# DAC.net
KiCad netlist of a schematic drawn in Altium Designer
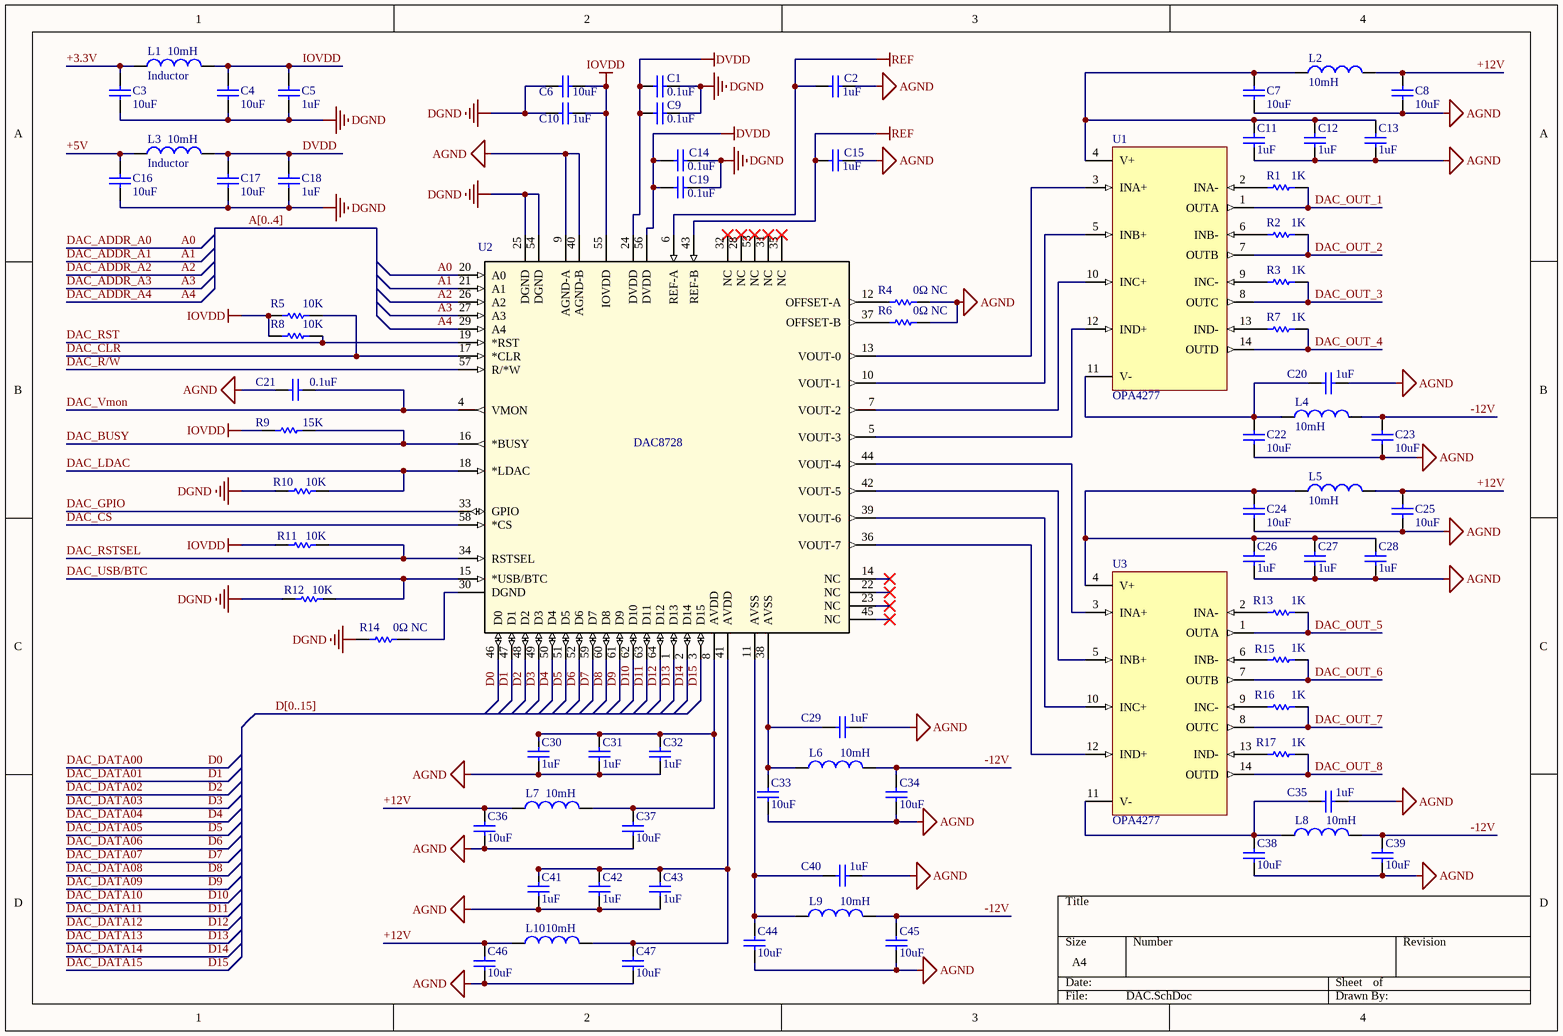
[diagram p0: DAC.SchDoc]

(export (version "E")
  (design (tool "Eeschema 10.0.6"))
  (components
    (comp (ref "C1")
      (value "0.1uF")
      (footprint "1608[0603]")
      (description "Capacitor")
      (fields (field (name "Comment") "Cap") (field (name "PUBLISHER") "Altium Limited"))
      (libsource (lib "Miscellaneous Devices") (part "Cap"))
    )
    (comp (ref "C2")
      (value "1uF")
      (footprint "1608[0603]")
      (description "Capacitor")
      (fields (field (name "Comment") "Cap") (field (name "PUBLISHER") "Altium Limited"))
      (libsource (lib "Miscellaneous Devices") (part "Cap"))
    )
    (comp (ref "C3")
      (value "10uF")
      (footprint "1608[0603]")
      (description "Capacitor")
      (fields (field (name "Comment") "Cap") (field (name "PUBLISHER") "Altium Limited"))
      (libsource (lib "Miscellaneous Devices") (part "Cap"))
    )
    (comp (ref "C4")
      (value "10uF")
      (footprint "1608[0603]")
      (description "Capacitor")
      (fields (field (name "Comment") "Cap") (field (name "PUBLISHER") "Altium Limited"))
      (libsource (lib "Miscellaneous Devices") (part "Cap"))
    )
    (comp (ref "C5")
      (value "1uF")
      (footprint "1608[0603]")
      (description "Capacitor")
      (fields (field (name "Comment") "Cap") (field (name "PUBLISHER") "Altium Limited"))
      (libsource (lib "Miscellaneous Devices") (part "Cap"))
    )
    (comp (ref "C6")
      (value "10uF")
      (footprint "1608[0603]")
      (description "Capacitor")
      (fields (field (name "Comment") "Cap") (field (name "PUBLISHER") "Altium Limited"))
      (libsource (lib "Miscellaneous Devices") (part "Cap"))
    )
    (comp (ref "C7")
      (value "10uF")
      (footprint "1608[0603]")
      (description "Capacitor")
      (fields (field (name "Comment") "Cap") (field (name "PUBLISHER") "Altium Limited"))
      (libsource (lib "Miscellaneous Devices") (part "Cap"))
    )
    (comp (ref "C8")
      (value "10uF")
      (footprint "1608[0603]")
      (description "Capacitor")
      (fields (field (name "Comment") "Cap") (field (name "PUBLISHER") "Altium Limited"))
      (libsource (lib "Miscellaneous Devices") (part "Cap"))
    )
    (comp (ref "C9")
      (value "0.1uF")
      (footprint "1608[0603]")
      (description "Capacitor")
      (fields (field (name "Comment") "Cap") (field (name "PUBLISHER") "Altium Limited"))
      (libsource (lib "Miscellaneous Devices") (part "Cap"))
    )
    (comp (ref "C10")
      (value "1uF")
      (footprint "1608[0603]")
      (description "Capacitor")
      (fields (field (name "Comment") "Cap") (field (name "PUBLISHER") "Altium Limited"))
      (libsource (lib "Miscellaneous Devices") (part "Cap"))
    )
    (comp (ref "C11")
      (value "1uF")
      (footprint "1608[0603]")
      (description "Capacitor")
      (fields (field (name "Comment") "Cap") (field (name "PUBLISHER") "Altium Limited"))
      (libsource (lib "Miscellaneous Devices") (part "Cap"))
    )
    (comp (ref "C12")
      (value "1uF")
      (footprint "1608[0603]")
      (description "Capacitor")
      (fields (field (name "Comment") "Cap") (field (name "PUBLISHER") "Altium Limited"))
      (libsource (lib "Miscellaneous Devices") (part "Cap"))
    )
    (comp (ref "C13")
      (value "1uF")
      (footprint "1608[0603]")
      (description "Capacitor")
      (fields (field (name "Comment") "Cap") (field (name "PUBLISHER") "Altium Limited"))
      (libsource (lib "Miscellaneous Devices") (part "Cap"))
    )
    (comp (ref "C14")
      (value "0.1uF")
      (footprint "1608[0603]")
      (description "Capacitor")
      (fields (field (name "Comment") "Cap") (field (name "PUBLISHER") "Altium Limited"))
      (libsource (lib "Miscellaneous Devices") (part "Cap"))
    )
    (comp (ref "C15")
      (value "1uF")
      (footprint "1608[0603]")
      (description "Capacitor")
      (fields (field (name "Comment") "Cap") (field (name "PUBLISHER") "Altium Limited"))
      (libsource (lib "Miscellaneous Devices") (part "Cap"))
    )
    (comp (ref "C16")
      (value "10uF")
      (footprint "1608[0603]")
      (description "Capacitor")
      (fields (field (name "Comment") "Cap") (field (name "PUBLISHER") "Altium Limited"))
      (libsource (lib "Miscellaneous Devices") (part "Cap"))
    )
    (comp (ref "C17")
      (value "10uF")
      (footprint "1608[0603]")
      (description "Capacitor")
      (fields (field (name "Comment") "Cap") (field (name "PUBLISHER") "Altium Limited"))
      (libsource (lib "Miscellaneous Devices") (part "Cap"))
    )
    (comp (ref "C18")
      (value "1uF")
      (footprint "1608[0603]")
      (description "Capacitor")
      (fields (field (name "Comment") "Cap") (field (name "PUBLISHER") "Altium Limited"))
      (libsource (lib "Miscellaneous Devices") (part "Cap"))
    )
    (comp (ref "C19")
      (value "0.1uF")
      (footprint "1608[0603]")
      (description "Capacitor")
      (fields (field (name "Comment") "Cap") (field (name "PUBLISHER") "Altium Limited"))
      (libsource (lib "Miscellaneous Devices") (part "Cap"))
    )
    (comp (ref "C20")
      (value "1uF")
      (footprint "1608[0603]")
      (description "Capacitor")
      (fields (field (name "Comment") "Cap") (field (name "PUBLISHER") "Altium Limited"))
      (libsource (lib "Miscellaneous Devices") (part "Cap"))
    )
    (comp (ref "C21")
      (value "0.1uF")
      (footprint "1608[0603]")
      (description "Capacitor")
      (fields (field (name "Comment") "Cap") (field (name "PUBLISHER") "Altium Limited"))
      (libsource (lib "Miscellaneous Devices") (part "Cap"))
    )
    (comp (ref "C22")
      (value "10uF")
      (footprint "1608[0603]")
      (description "Capacitor")
      (fields (field (name "Comment") "Cap") (field (name "PUBLISHER") "Altium Limited"))
      (libsource (lib "Miscellaneous Devices") (part "Cap"))
    )
    (comp (ref "C23")
      (value "10uF")
      (footprint "1608[0603]")
      (description "Capacitor")
      (fields (field (name "Comment") "Cap") (field (name "PUBLISHER") "Altium Limited"))
      (libsource (lib "Miscellaneous Devices") (part "Cap"))
    )
    (comp (ref "C24")
      (value "10uF")
      (footprint "1608[0603]")
      (description "Capacitor")
      (fields (field (name "Comment") "Cap") (field (name "PUBLISHER") "Altium Limited"))
      (libsource (lib "Miscellaneous Devices") (part "Cap"))
    )
    (comp (ref "C25")
      (value "10uF")
      (footprint "1608[0603]")
      (description "Capacitor")
      (fields (field (name "Comment") "Cap") (field (name "PUBLISHER") "Altium Limited"))
      (libsource (lib "Miscellaneous Devices") (part "Cap"))
    )
    (comp (ref "C26")
      (value "1uF")
      (footprint "1608[0603]")
      (description "Capacitor")
      (fields (field (name "Comment") "Cap") (field (name "PUBLISHER") "Altium Limited"))
      (libsource (lib "Miscellaneous Devices") (part "Cap"))
    )
    (comp (ref "C27")
      (value "1uF")
      (footprint "1608[0603]")
      (description "Capacitor")
      (fields (field (name "Comment") "Cap") (field (name "PUBLISHER") "Altium Limited"))
      (libsource (lib "Miscellaneous Devices") (part "Cap"))
    )
    (comp (ref "C28")
      (value "1uF")
      (footprint "1608[0603]")
      (description "Capacitor")
      (fields (field (name "Comment") "Cap") (field (name "PUBLISHER") "Altium Limited"))
      (libsource (lib "Miscellaneous Devices") (part "Cap"))
    )
    (comp (ref "C29")
      (value "1uF")
      (footprint "1608[0603]")
      (description "Capacitor")
      (fields (field (name "Comment") "Cap") (field (name "PUBLISHER") "Altium Limited"))
      (libsource (lib "Miscellaneous Devices") (part "Cap"))
    )
    (comp (ref "C30")
      (value "1uF")
      (footprint "1608[0603]")
      (description "Capacitor")
      (fields (field (name "Comment") "Cap") (field (name "PUBLISHER") "Altium Limited"))
      (libsource (lib "Miscellaneous Devices") (part "Cap"))
    )
    (comp (ref "C31")
      (value "1uF")
      (footprint "1608[0603]")
      (description "Capacitor")
      (fields (field (name "Comment") "Cap") (field (name "PUBLISHER") "Altium Limited"))
      (libsource (lib "Miscellaneous Devices") (part "Cap"))
    )
    (comp (ref "C32")
      (value "1uF")
      (footprint "1608[0603]")
      (description "Capacitor")
      (fields (field (name "Comment") "Cap") (field (name "PUBLISHER") "Altium Limited"))
      (libsource (lib "Miscellaneous Devices") (part "Cap"))
    )
    (comp (ref "C33")
      (value "10uF")
      (footprint "1608[0603]")
      (description "Capacitor")
      (fields (field (name "Comment") "Cap") (field (name "PUBLISHER") "Altium Limited"))
      (libsource (lib "Miscellaneous Devices") (part "Cap"))
    )
    (comp (ref "C34")
      (value "10uF")
      (footprint "1608[0603]")
      (description "Capacitor")
      (fields (field (name "Comment") "Cap") (field (name "PUBLISHER") "Altium Limited"))
      (libsource (lib "Miscellaneous Devices") (part "Cap"))
    )
    (comp (ref "C35")
      (value "1uF")
      (footprint "1608[0603]")
      (description "Capacitor")
      (fields (field (name "Comment") "Cap") (field (name "PUBLISHER") "Altium Limited"))
      (libsource (lib "Miscellaneous Devices") (part "Cap"))
    )
    (comp (ref "C36")
      (value "10uF")
      (footprint "1608[0603]")
      (description "Capacitor")
      (fields (field (name "Comment") "Cap") (field (name "PUBLISHER") "Altium Limited"))
      (libsource (lib "Miscellaneous Devices") (part "Cap"))
    )
    (comp (ref "C37")
      (value "10uF")
      (footprint "1608[0603]")
      (description "Capacitor")
      (fields (field (name "Comment") "Cap") (field (name "PUBLISHER") "Altium Limited"))
      (libsource (lib "Miscellaneous Devices") (part "Cap"))
    )
    (comp (ref "C38")
      (value "10uF")
      (footprint "1608[0603]")
      (description "Capacitor")
      (fields (field (name "Comment") "Cap") (field (name "PUBLISHER") "Altium Limited"))
      (libsource (lib "Miscellaneous Devices") (part "Cap"))
    )
    (comp (ref "C39")
      (value "10uF")
      (footprint "1608[0603]")
      (description "Capacitor")
      (fields (field (name "Comment") "Cap") (field (name "PUBLISHER") "Altium Limited"))
      (libsource (lib "Miscellaneous Devices") (part "Cap"))
    )
    (comp (ref "C40")
      (value "1uF")
      (footprint "1608[0603]")
      (description "Capacitor")
      (fields (field (name "Comment") "Cap") (field (name "PUBLISHER") "Altium Limited"))
      (libsource (lib "Miscellaneous Devices") (part "Cap"))
    )
    (comp (ref "C41")
      (value "1uF")
      (footprint "1608[0603]")
      (description "Capacitor")
      (fields (field (name "Comment") "Cap") (field (name "PUBLISHER") "Altium Limited"))
      (libsource (lib "Miscellaneous Devices") (part "Cap"))
    )
    (comp (ref "C42")
      (value "1uF")
      (footprint "1608[0603]")
      (description "Capacitor")
      (fields (field (name "Comment") "Cap") (field (name "PUBLISHER") "Altium Limited"))
      (libsource (lib "Miscellaneous Devices") (part "Cap"))
    )
    (comp (ref "C43")
      (value "1uF")
      (footprint "1608[0603]")
      (description "Capacitor")
      (fields (field (name "Comment") "Cap") (field (name "PUBLISHER") "Altium Limited"))
      (libsource (lib "Miscellaneous Devices") (part "Cap"))
    )
    (comp (ref "C44")
      (value "10uF")
      (footprint "1608[0603]")
      (description "Capacitor")
      (fields (field (name "Comment") "Cap") (field (name "PUBLISHER") "Altium Limited"))
      (libsource (lib "Miscellaneous Devices") (part "Cap"))
    )
    (comp (ref "C45")
      (value "10uF")
      (footprint "1608[0603]")
      (description "Capacitor")
      (fields (field (name "Comment") "Cap") (field (name "PUBLISHER") "Altium Limited"))
      (libsource (lib "Miscellaneous Devices") (part "Cap"))
    )
    (comp (ref "C46")
      (value "10uF")
      (footprint "1608[0603]")
      (description "Capacitor")
      (fields (field (name "Comment") "Cap") (field (name "PUBLISHER") "Altium Limited"))
      (libsource (lib "Miscellaneous Devices") (part "Cap"))
    )
    (comp (ref "C47")
      (value "10uF")
      (footprint "1608[0603]")
      (description "Capacitor")
      (fields (field (name "Comment") "Cap") (field (name "PUBLISHER") "Altium Limited"))
      (libsource (lib "Miscellaneous Devices") (part "Cap"))
    )
    (comp (ref "L1")
      (value "Inductor")
      (footprint "2029")
      (fields (field (name "ALTIUM_VALUE") "10mH") (field (name "PUBLISHER") "Altium Limited"))
      (libsource (lib "Miscellaneous Devices") (part "Inductor"))
    )
    (comp (ref "L2")
      (value "10mH")
      (footprint "2029")
      (description "Inductor")
      (fields (field (name "PUBLISHER") "Altium Limited"))
      (libsource (lib "") (part "Inductor_1"))
    )
    (comp (ref "L3")
      (value "Inductor")
      (footprint "2029")
      (fields (field (name "ALTIUM_VALUE") "10mH") (field (name "PUBLISHER") "Altium Limited"))
      (libsource (lib "Miscellaneous Devices") (part "Inductor"))
    )
    (comp (ref "L4")
      (value "10mH")
      (footprint "2029")
      (description "Inductor")
      (fields (field (name "PUBLISHER") "Altium Limited"))
      (libsource (lib "Miscellaneous Devices") (part "Inductor"))
    )
    (comp (ref "L5")
      (value "10mH")
      (footprint "2029")
      (description "Inductor")
      (fields (field (name "PUBLISHER") "Altium Limited"))
      (libsource (lib "") (part "Inductor_1"))
    )
    (comp (ref "L6")
      (value "10mH")
      (footprint "2029")
      (description "Inductor")
      (fields (field (name "PUBLISHER") "Altium Limited"))
      (libsource (lib "Miscellaneous Devices") (part "Inductor"))
    )
    (comp (ref "L7")
      (value "10mH")
      (footprint "2029")
      (description "Inductor")
      (fields (field (name "PUBLISHER") "Altium Limited"))
      (libsource (lib "Miscellaneous Devices") (part "Inductor"))
    )
    (comp (ref "L8")
      (value "10mH")
      (footprint "2029")
      (description "Inductor")
      (fields (field (name "PUBLISHER") "Altium Limited"))
      (libsource (lib "Miscellaneous Devices") (part "Inductor"))
    )
    (comp (ref "L9")
      (value "10mH")
      (footprint "2029")
      (description "Inductor")
      (fields (field (name "PUBLISHER") "Altium Limited"))
      (libsource (lib "Miscellaneous Devices") (part "Inductor"))
    )
    (comp (ref "L10")
      (value "10mH")
      (footprint "2029")
      (description "Inductor")
      (fields (field (name "PUBLISHER") "Altium Limited"))
      (libsource (lib "Miscellaneous Devices") (part "Inductor"))
    )
    (comp (ref "R1")
      (value "1K")
      (footprint "1608[0603]")
      (description "Resistor")
      (fields (field (name "Comment") "Res1") (field (name "PUBLISHER") "Altium Limited"))
      (libsource (lib "Miscellaneous Devices") (part "Res1"))
    )
    (comp (ref "R2")
      (value "1K")
      (footprint "1608[0603]")
      (description "Resistor")
      (fields (field (name "Comment") "Res1") (field (name "PUBLISHER") "Altium Limited"))
      (libsource (lib "Miscellaneous Devices") (part "Res1"))
    )
    (comp (ref "R3")
      (value "1K")
      (footprint "1608[0603]")
      (description "Resistor")
      (fields (field (name "Comment") "Res1") (field (name "PUBLISHER") "Altium Limited"))
      (libsource (lib "Miscellaneous Devices") (part "Res1"))
    )
    (comp (ref "R4")
      (value "0Ω NC")
      (footprint "1608[0603]")
      (description "Resistor")
      (fields (field (name "Comment") "Res1") (field (name "PUBLISHER") "Altium Limited"))
      (libsource (lib "Miscellaneous Devices") (part "Res1"))
    )
    (comp (ref "R5")
      (value "10K")
      (footprint "1608[0603]")
      (description "Resistor")
      (fields (field (name "Comment") "Res1") (field (name "PUBLISHER") "Altium Limited"))
      (libsource (lib "Miscellaneous Devices") (part "Res1"))
    )
    (comp (ref "R6")
      (value "0Ω NC")
      (footprint "1608[0603]")
      (description "Resistor")
      (fields (field (name "Comment") "Res1") (field (name "PUBLISHER") "Altium Limited"))
      (libsource (lib "Miscellaneous Devices") (part "Res1"))
    )
    (comp (ref "R7")
      (value "1K")
      (footprint "1608[0603]")
      (description "Resistor")
      (fields (field (name "Comment") "Res1") (field (name "PUBLISHER") "Altium Limited"))
      (libsource (lib "Miscellaneous Devices") (part "Res1"))
    )
    (comp (ref "R8")
      (value "10K")
      (footprint "1608[0603]")
      (description "Resistor")
      (fields (field (name "Comment") "Res1") (field (name "PUBLISHER") "Altium Limited"))
      (libsource (lib "Miscellaneous Devices") (part "Res1"))
    )
    (comp (ref "R9")
      (value "15K")
      (footprint "1608[0603]")
      (description "Resistor")
      (fields (field (name "Comment") "Res1") (field (name "PUBLISHER") "Altium Limited"))
      (libsource (lib "Miscellaneous Devices") (part "Res1"))
    )
    (comp (ref "R10")
      (value "10K")
      (footprint "1608[0603]")
      (description "Resistor")
      (fields (field (name "Comment") "Res1") (field (name "PUBLISHER") "Altium Limited"))
      (libsource (lib "Miscellaneous Devices") (part "Res1"))
    )
    (comp (ref "R11")
      (value "10K")
      (footprint "1608[0603]")
      (description "Resistor")
      (fields (field (name "Comment") "Res1") (field (name "PUBLISHER") "Altium Limited"))
      (libsource (lib "Miscellaneous Devices") (part "Res1"))
    )
    (comp (ref "R12")
      (value "10K")
      (footprint "1608[0603]")
      (description "Resistor")
      (fields (field (name "Comment") "Res1") (field (name "PUBLISHER") "Altium Limited"))
      (libsource (lib "Miscellaneous Devices") (part "Res1"))
    )
    (comp (ref "R13")
      (value "1K")
      (footprint "1608[0603]")
      (description "Resistor")
      (fields (field (name "Comment") "Res1") (field (name "PUBLISHER") "Altium Limited"))
      (libsource (lib "Miscellaneous Devices") (part "Res1"))
    )
    (comp (ref "R14")
      (value "0Ω NC")
      (footprint "1608[0603]")
      (description "Resistor")
      (fields (field (name "Comment") "Res1") (field (name "PUBLISHER") "Altium Limited"))
      (libsource (lib "Miscellaneous Devices") (part "Res1"))
    )
    (comp (ref "R15")
      (value "1K")
      (footprint "1608[0603]")
      (description "Resistor")
      (fields (field (name "Comment") "Res1") (field (name "PUBLISHER") "Altium Limited"))
      (libsource (lib "Miscellaneous Devices") (part "Res1"))
    )
    (comp (ref "R16")
      (value "1K")
      (footprint "1608[0603]")
      (description "Resistor")
      (fields (field (name "Comment") "Res1") (field (name "PUBLISHER") "Altium Limited"))
      (libsource (lib "Miscellaneous Devices") (part "Res1"))
    )
    (comp (ref "R17")
      (value "1K")
      (footprint "1608[0603]")
      (description "Resistor")
      (fields (field (name "Comment") "Res1") (field (name "PUBLISHER") "Altium Limited"))
      (libsource (lib "Miscellaneous Devices") (part "Res1"))
    )
    (comp (ref "U1")
      (value "OPA4277")
      (footprint "OPA4277_SOIC")
      (libsource (lib "DSP_FPGA_Lib") (part "OPA4277"))
    )
    (comp (ref "U2")
      (value "DAC8728")
      (footprint "DAC8728")
      (libsource (lib "DSP_FPGA_Lib") (part "DAC8728"))
    )
    (comp (ref "U3")
      (value "OPA4277")
      (footprint "OPA4277_SOIC")
      (libsource (lib "DSP_FPGA_Lib") (part "OPA4277"))
    )
  )
  (nets
    (net (code "1") (name "/+3.3V") (class "Default")
      (node (ref "C3") (pin "2") (pinfunction "2_2") (pintype "passive"))
      (node (ref "L1") (pin "1") (pinfunction "1_1") (pintype "passive"))
    )
    (net (code "2") (name "/+5V") (class "Default")
      (node (ref "C16") (pin "2") (pinfunction "2_2") (pintype "passive"))
      (node (ref "L3") (pin "1") (pinfunction "1_1") (pintype "passive"))
    )
    (net (code "3") (name "/+12V") (class "Default")
      (node (ref "C25") (pin "1") (pinfunction "1_1") (pintype "passive"))
      (node (ref "C36") (pin "1") (pinfunction "1_1") (pintype "passive"))
      (node (ref "C46") (pin "1") (pinfunction "1_1") (pintype "passive"))
      (node (ref "C8") (pin "1") (pinfunction "1_1") (pintype "passive"))
      (node (ref "L10") (pin "1") (pinfunction "1_1") (pintype "passive"))
      (node (ref "L2") (pin "1") (pinfunction "1_1") (pintype "passive"))
      (node (ref "L5") (pin "1") (pinfunction "1_1") (pintype "passive"))
      (node (ref "L7") (pin "1") (pinfunction "1_1") (pintype "passive"))
    )
    (net (code "4") (name "/-12V") (class "Default")
      (node (ref "C23") (pin "1") (pinfunction "1_1") (pintype "passive"))
      (node (ref "C34") (pin "1") (pinfunction "1_1") (pintype "passive"))
      (node (ref "C39") (pin "1") (pinfunction "1_1") (pintype "passive"))
      (node (ref "C45") (pin "1") (pinfunction "1_1") (pintype "passive"))
      (node (ref "L4") (pin "2") (pinfunction "2_2") (pintype "passive"))
      (node (ref "L6") (pin "2") (pinfunction "2_2") (pintype "passive"))
      (node (ref "L8") (pin "2") (pinfunction "2_2") (pintype "passive"))
      (node (ref "L9") (pin "2") (pinfunction "2_2") (pintype "passive"))
    )
    (net (code "5") (name "/A0") (class "Default")
      (node (ref "U2") (pin "20") (pinfunction "A0_20") (pintype "input"))
    )
    (net (code "6") (name "/A1") (class "Default")
      (node (ref "U2") (pin "21") (pinfunction "A1_21") (pintype "input"))
    )
    (net (code "7") (name "/A2") (class "Default")
      (node (ref "U2") (pin "26") (pinfunction "A2_26") (pintype "input"))
    )
    (net (code "8") (name "/A3") (class "Default")
      (node (ref "U2") (pin "27") (pinfunction "A3_27") (pintype "input"))
    )
    (net (code "9") (name "/A4") (class "Default")
      (node (ref "U2") (pin "29") (pinfunction "A4_29") (pintype "input"))
    )
    (net (code "11") (name "/D0") (class "Default")
      (node (ref "U2") (pin "46") (pinfunction "D0_46") (pintype "bidirectional"))
    )
    (net (code "12") (name "/D1") (class "Default")
      (node (ref "U2") (pin "47") (pinfunction "D1_47") (pintype "bidirectional"))
    )
    (net (code "13") (name "/D2") (class "Default")
      (node (ref "U2") (pin "48") (pinfunction "D2_48") (pintype "bidirectional"))
    )
    (net (code "14") (name "/D3") (class "Default")
      (node (ref "U2") (pin "49") (pinfunction "D3_49") (pintype "bidirectional"))
    )
    (net (code "15") (name "/D4") (class "Default")
      (node (ref "U2") (pin "50") (pinfunction "D4_50") (pintype "bidirectional"))
    )
    (net (code "16") (name "/D5") (class "Default")
      (node (ref "U2") (pin "51") (pinfunction "D5_51") (pintype "bidirectional"))
    )
    (net (code "17") (name "/D6") (class "Default")
      (node (ref "U2") (pin "52") (pinfunction "D6_52") (pintype "bidirectional"))
    )
    (net (code "18") (name "/D7") (class "Default")
      (node (ref "U2") (pin "59") (pinfunction "D7_59") (pintype "bidirectional"))
    )
    (net (code "19") (name "/D8") (class "Default")
      (node (ref "U2") (pin "60") (pinfunction "D8_60") (pintype "bidirectional"))
    )
    (net (code "20") (name "/D9") (class "Default")
      (node (ref "U2") (pin "61") (pinfunction "D9_61") (pintype "bidirectional"))
    )
    (net (code "21") (name "/D10") (class "Default")
      (node (ref "U2") (pin "62") (pinfunction "D10_62") (pintype "bidirectional"))
    )
    (net (code "22") (name "/D11") (class "Default")
      (node (ref "U2") (pin "63") (pinfunction "D11_63") (pintype "bidirectional"))
    )
    (net (code "23") (name "/D12") (class "Default")
      (node (ref "U2") (pin "64") (pinfunction "D12_64") (pintype "bidirectional"))
    )
    (net (code "24") (name "/D13") (class "Default")
      (node (ref "U2") (pin "1") (pinfunction "D13_1") (pintype "bidirectional"))
    )
    (net (code "25") (name "/D14") (class "Default")
      (node (ref "U2") (pin "2") (pinfunction "D14_2") (pintype "bidirectional"))
    )
    (net (code "26") (name "/D15") (class "Default")
      (node (ref "U2") (pin "3") (pinfunction "D15_3") (pintype "bidirectional"))
    )
    (net (code "27") (name "/DAC_BUSY") (class "Default")
      (node (ref "R9") (pin "1") (pinfunction "1_1") (pintype "passive"))
      (node (ref "U2") (pin "16") (pinfunction "*BUSY_16") (pintype "output"))
    )
    (net (code "28") (name "/DAC_CLR") (class "Default")
      (node (ref "R5") (pin "2") (pinfunction "2_2") (pintype "passive"))
      (node (ref "U2") (pin "17") (pinfunction "*CLR_17") (pintype "input"))
    )
    (net (code "29") (name "/DAC_CS") (class "Default")
      (node (ref "U2") (pin "58") (pinfunction "*CS_58") (pintype "input"))
    )
    (net (code "30") (name "/DAC_GPIO") (class "Default")
      (node (ref "U2") (pin "33") (pinfunction "GPIO_33") (pintype "bidirectional"))
    )
    (net (code "31") (name "/DAC_LDAC") (class "Default")
      (node (ref "R10") (pin "1") (pinfunction "1_1") (pintype "passive"))
      (node (ref "U2") (pin "18") (pinfunction "*LDAC_18") (pintype "input"))
    )
    (net (code "32") (name "/DAC_OUT_1") (class "Default")
      (node (ref "R1") (pin "2") (pinfunction "2_2") (pintype "passive"))
      (node (ref "U1") (pin "1") (pinfunction "OUTA_1") (pintype "output"))
    )
    (net (code "33") (name "/DAC_OUT_2") (class "Default")
      (node (ref "R2") (pin "2") (pinfunction "2_2") (pintype "passive"))
      (node (ref "U1") (pin "7") (pinfunction "OUTB_7") (pintype "output"))
    )
    (net (code "34") (name "/DAC_OUT_3") (class "Default")
      (node (ref "R3") (pin "2") (pinfunction "2_2") (pintype "passive"))
      (node (ref "U1") (pin "8") (pinfunction "OUTC_8") (pintype "output"))
    )
    (net (code "35") (name "/DAC_OUT_4") (class "Default")
      (node (ref "R7") (pin "2") (pinfunction "2_2") (pintype "passive"))
      (node (ref "U1") (pin "14") (pinfunction "OUTD_14") (pintype "output"))
    )
    (net (code "36") (name "/DAC_OUT_5") (class "Default")
      (node (ref "R13") (pin "2") (pinfunction "2_2") (pintype "passive"))
      (node (ref "U3") (pin "1") (pinfunction "OUTA_1") (pintype "output"))
    )
    (net (code "37") (name "/DAC_OUT_6") (class "Default")
      (node (ref "R15") (pin "2") (pinfunction "2_2") (pintype "passive"))
      (node (ref "U3") (pin "7") (pinfunction "OUTB_7") (pintype "output"))
    )
    (net (code "38") (name "/DAC_OUT_7") (class "Default")
      (node (ref "R16") (pin "2") (pinfunction "2_2") (pintype "passive"))
      (node (ref "U3") (pin "8") (pinfunction "OUTC_8") (pintype "output"))
    )
    (net (code "39") (name "/DAC_OUT_8") (class "Default")
      (node (ref "R17") (pin "2") (pinfunction "2_2") (pintype "passive"))
      (node (ref "U3") (pin "14") (pinfunction "OUTD_14") (pintype "output"))
    )
    (net (code "40") (name "/DAC_RST") (class "Default")
      (node (ref "R8") (pin "2") (pinfunction "2_2") (pintype "passive"))
      (node (ref "U2") (pin "19") (pinfunction "*RST_19") (pintype "input"))
    )
    (net (code "41") (name "/DAC_RSTSEL") (class "Default")
      (node (ref "R11") (pin "1") (pinfunction "1_1") (pintype "passive"))
      (node (ref "U2") (pin "34") (pinfunction "RSTSEL_34") (pintype "input"))
    )
    (net (code "42") (name "/DAC_R{slash}W") (class "Default")
      (node (ref "U2") (pin "57") (pinfunction "R/*W_57") (pintype "input"))
    )
    (net (code "43") (name "/DAC_USB{slash}BTC") (class "Default")
      (node (ref "R12") (pin "1") (pinfunction "1_1") (pintype "passive"))
      (node (ref "U2") (pin "15") (pinfunction "*USB/BTC_15") (pintype "input"))
    )
    (net (code "44") (name "/DAC_Vmon") (class "Default")
      (node (ref "C21") (pin "1") (pinfunction "1_1") (pintype "passive"))
      (node (ref "U2") (pin "4") (pinfunction "VMON_4") (pintype "output"))
    )
    (net (code "46") (name "AGND") (class "Default")
      (node (ref "C11") (pin "2") (pinfunction "2_2") (pintype "passive"))
      (node (ref "C12") (pin "2") (pinfunction "2_2") (pintype "passive"))
      (node (ref "C13") (pin "2") (pinfunction "2_2") (pintype "passive"))
      (node (ref "C15") (pin "1") (pinfunction "1_1") (pintype "passive"))
      (node (ref "C2") (pin "1") (pinfunction "1_1") (pintype "passive"))
      (node (ref "C20") (pin "2") (pinfunction "2_2") (pintype "passive"))
      (node (ref "C21") (pin "2") (pinfunction "2_2") (pintype "passive"))
      (node (ref "C22") (pin "2") (pinfunction "2_2") (pintype "passive"))
      (node (ref "C23") (pin "2") (pinfunction "2_2") (pintype "passive"))
      (node (ref "C24") (pin "2") (pinfunction "2_2") (pintype "passive"))
      (node (ref "C25") (pin "2") (pinfunction "2_2") (pintype "passive"))
      (node (ref "C26") (pin "2") (pinfunction "2_2") (pintype "passive"))
      (node (ref "C27") (pin "2") (pinfunction "2_2") (pintype "passive"))
      (node (ref "C28") (pin "2") (pinfunction "2_2") (pintype "passive"))
      (node (ref "C29") (pin "2") (pinfunction "2_2") (pintype "passive"))
      (node (ref "C30") (pin "2") (pinfunction "2_2") (pintype "passive"))
      (node (ref "C31") (pin "2") (pinfunction "2_2") (pintype "passive"))
      (node (ref "C32") (pin "2") (pinfunction "2_2") (pintype "passive"))
      (node (ref "C33") (pin "2") (pinfunction "2_2") (pintype "passive"))
      (node (ref "C34") (pin "2") (pinfunction "2_2") (pintype "passive"))
      (node (ref "C35") (pin "2") (pinfunction "2_2") (pintype "passive"))
      (node (ref "C36") (pin "2") (pinfunction "2_2") (pintype "passive"))
      (node (ref "C37") (pin "2") (pinfunction "2_2") (pintype "passive"))
      (node (ref "C38") (pin "2") (pinfunction "2_2") (pintype "passive"))
      (node (ref "C39") (pin "2") (pinfunction "2_2") (pintype "passive"))
      (node (ref "C40") (pin "2") (pinfunction "2_2") (pintype "passive"))
      (node (ref "C41") (pin "2") (pinfunction "2_2") (pintype "passive"))
      (node (ref "C42") (pin "2") (pinfunction "2_2") (pintype "passive"))
      (node (ref "C43") (pin "2") (pinfunction "2_2") (pintype "passive"))
      (node (ref "C44") (pin "2") (pinfunction "2_2") (pintype "passive"))
      (node (ref "C45") (pin "2") (pinfunction "2_2") (pintype "passive"))
      (node (ref "C46") (pin "2") (pinfunction "2_2") (pintype "passive"))
      (node (ref "C47") (pin "2") (pinfunction "2_2") (pintype "passive"))
      (node (ref "C7") (pin "2") (pinfunction "2_2") (pintype "passive"))
      (node (ref "C8") (pin "2") (pinfunction "2_2") (pintype "passive"))
      (node (ref "R4") (pin "2") (pinfunction "2_2") (pintype "passive"))
      (node (ref "R6") (pin "2") (pinfunction "2_2") (pintype "passive"))
      (node (ref "U2") (pin "40") (pinfunction "AGND-B_40") (pintype "power_in"))
      (node (ref "U2") (pin "9") (pinfunction "AGND-A_9") (pintype "power_in"))
    )
    (net (code "47") (name "DGND") (class "Default")
      (node (ref "C1") (pin "2") (pinfunction "2_2") (pintype "passive"))
      (node (ref "C10") (pin "2") (pinfunction "2_2") (pintype "passive"))
      (node (ref "C14") (pin "2") (pinfunction "2_2") (pintype "passive"))
      (node (ref "C16") (pin "1") (pinfunction "1_1") (pintype "passive"))
      (node (ref "C17") (pin "1") (pinfunction "1_1") (pintype "passive"))
      (node (ref "C18") (pin "1") (pinfunction "1_1") (pintype "passive"))
      (node (ref "C19") (pin "1") (pinfunction "1_1") (pintype "passive"))
      (node (ref "C3") (pin "1") (pinfunction "1_1") (pintype "passive"))
      (node (ref "C4") (pin "1") (pinfunction "1_1") (pintype "passive"))
      (node (ref "C5") (pin "1") (pinfunction "1_1") (pintype "passive"))
      (node (ref "C6") (pin "1") (pinfunction "1_1") (pintype "passive"))
      (node (ref "C9") (pin "1") (pinfunction "1_1") (pintype "passive"))
      (node (ref "R10") (pin "2") (pinfunction "2_2") (pintype "passive"))
      (node (ref "R12") (pin "2") (pinfunction "2_2") (pintype "passive"))
      (node (ref "R14") (pin "1") (pinfunction "1_1") (pintype "passive"))
      (node (ref "U2") (pin "25") (pinfunction "DGND_25") (pintype "power_in"))
      (node (ref "U2") (pin "54") (pinfunction "DGND_54") (pintype "power_in"))
    )
    (net (code "48") (name "DVDD") (class "Default")
      (node (ref "C1") (pin "1") (pinfunction "1_1") (pintype "passive"))
      (node (ref "C14") (pin "1") (pinfunction "1_1") (pintype "passive"))
      (node (ref "C17") (pin "2") (pinfunction "2_2") (pintype "passive"))
      (node (ref "C18") (pin "2") (pinfunction "2_2") (pintype "passive"))
      (node (ref "C19") (pin "2") (pinfunction "2_2") (pintype "passive"))
      (node (ref "C9") (pin "2") (pinfunction "2_2") (pintype "passive"))
      (node (ref "L3") (pin "2") (pinfunction "2_2") (pintype "passive"))
      (node (ref "U2") (pin "24") (pinfunction "DVDD_24") (pintype "power_in"))
      (node (ref "U2") (pin "56") (pinfunction "DVDD_56") (pintype "power_in"))
    )
    (net (code "49") (name "IOVDD") (class "Default")
      (node (ref "C10") (pin "1") (pinfunction "1_1") (pintype "passive"))
      (node (ref "C4") (pin "2") (pinfunction "2_2") (pintype "passive"))
      (node (ref "C5") (pin "2") (pinfunction "2_2") (pintype "passive"))
      (node (ref "C6") (pin "2") (pinfunction "2_2") (pintype "passive"))
      (node (ref "L1") (pin "2") (pinfunction "2_2") (pintype "passive"))
      (node (ref "R11") (pin "2") (pinfunction "2_2") (pintype "passive"))
      (node (ref "R5") (pin "1") (pinfunction "1_1") (pintype "passive"))
      (node (ref "R8") (pin "1") (pinfunction "1_1") (pintype "passive"))
      (node (ref "R9") (pin "2") (pinfunction "2_2") (pintype "passive"))
      (node (ref "U2") (pin "55") (pinfunction "IOVDD_55") (pintype "power_in"))
    )
    (net (code "50") (name "Net-(C29-Pad1)") (class "Default")
      (node (ref "C29") (pin "1") (pinfunction "1_1") (pintype "passive"))
      (node (ref "C33") (pin "1") (pinfunction "1_1") (pintype "passive"))
      (node (ref "L6") (pin "1") (pinfunction "1_1") (pintype "passive"))
      (node (ref "U2") (pin "38") (pinfunction "AVSS_38") (pintype "power_in"))
    )
    (net (code "51") (name "Net-(C30-Pad1)") (class "Default")
      (node (ref "C30") (pin "1") (pinfunction "1_1") (pintype "passive"))
      (node (ref "C31") (pin "1") (pinfunction "1_1") (pintype "passive"))
      (node (ref "C32") (pin "1") (pinfunction "1_1") (pintype "passive"))
      (node (ref "C37") (pin "1") (pinfunction "1_1") (pintype "passive"))
      (node (ref "L7") (pin "2") (pinfunction "2_2") (pintype "passive"))
      (node (ref "U2") (pin "8") (pinfunction "AVDD_8") (pintype "power_in"))
    )
    (net (code "52") (name "Net-(C40-Pad1)") (class "Default")
      (node (ref "C40") (pin "1") (pinfunction "1_1") (pintype "passive"))
      (node (ref "C44") (pin "1") (pinfunction "1_1") (pintype "passive"))
      (node (ref "L9") (pin "1") (pinfunction "1_1") (pintype "passive"))
      (node (ref "U2") (pin "11") (pinfunction "AVSS_11") (pintype "power_in"))
    )
    (net (code "53") (name "Net-(C41-Pad1)") (class "Default")
      (node (ref "C41") (pin "1") (pinfunction "1_1") (pintype "passive"))
      (node (ref "C42") (pin "1") (pinfunction "1_1") (pintype "passive"))
      (node (ref "C43") (pin "1") (pinfunction "1_1") (pintype "passive"))
      (node (ref "C47") (pin "1") (pinfunction "1_1") (pintype "passive"))
      (node (ref "L10") (pin "2") (pinfunction "2_2") (pintype "passive"))
      (node (ref "U2") (pin "41") (pinfunction "AVDD_41") (pintype "power_in"))
    )
    (net (code "54") (name "Net-(R14-Pad2)") (class "Default")
      (node (ref "R14") (pin "2") (pinfunction "2_2") (pintype "passive"))
      (node (ref "U2") (pin "30") (pinfunction "DGND_30") (pintype "power_in"))
    )
    (net (code "55") (name "Net-(U1-INA+)") (class "Default")
      (node (ref "U1") (pin "3") (pinfunction "INA+_3") (pintype "input"))
      (node (ref "U2") (pin "13") (pinfunction "VOUT-0_13") (pintype "output"))
    )
    (net (code "56") (name "Net-(U1-INA-)") (class "Default")
      (node (ref "R1") (pin "1") (pinfunction "1_1") (pintype "passive"))
      (node (ref "U1") (pin "2") (pinfunction "INA-_2") (pintype "input"))
    )
    (net (code "57") (name "Net-(U1-INB+)") (class "Default")
      (node (ref "U1") (pin "5") (pinfunction "INB+_5") (pintype "input"))
      (node (ref "U2") (pin "10") (pinfunction "VOUT-1_10") (pintype "output"))
    )
    (net (code "58") (name "Net-(U1-INB-)") (class "Default")
      (node (ref "R2") (pin "1") (pinfunction "1_1") (pintype "passive"))
      (node (ref "U1") (pin "6") (pinfunction "INB-_6") (pintype "input"))
    )
    (net (code "59") (name "Net-(U1-INC+)") (class "Default")
      (node (ref "U1") (pin "10") (pinfunction "INC+_10") (pintype "input"))
      (node (ref "U2") (pin "7") (pinfunction "VOUT-2_7") (pintype "output"))
    )
    (net (code "60") (name "Net-(U1-INC-)") (class "Default")
      (node (ref "R3") (pin "1") (pinfunction "1_1") (pintype "passive"))
      (node (ref "U1") (pin "9") (pinfunction "INC-_9") (pintype "input"))
    )
    (net (code "61") (name "Net-(U1-IND+)") (class "Default")
      (node (ref "U1") (pin "12") (pinfunction "IND+_12") (pintype "input"))
      (node (ref "U2") (pin "5") (pinfunction "VOUT-3_5") (pintype "output"))
    )
    (net (code "62") (name "Net-(U1-IND-)") (class "Default")
      (node (ref "R7") (pin "1") (pinfunction "1_1") (pintype "passive"))
      (node (ref "U1") (pin "13") (pinfunction "IND-_13") (pintype "input"))
    )
    (net (code "63") (name "Net-(U1-V+)") (class "Default")
      (node (ref "C11") (pin "1") (pinfunction "1_1") (pintype "passive"))
      (node (ref "C12") (pin "1") (pinfunction "1_1") (pintype "passive"))
      (node (ref "C13") (pin "1") (pinfunction "1_1") (pintype "passive"))
      (node (ref "C7") (pin "1") (pinfunction "1_1") (pintype "passive"))
      (node (ref "L2") (pin "2") (pinfunction "2_2") (pintype "passive"))
      (node (ref "U1") (pin "4") (pinfunction "V+_4") (pintype "power_in"))
    )
    (net (code "64") (name "Net-(U1-V-)") (class "Default")
      (node (ref "C20") (pin "1") (pinfunction "1_1") (pintype "passive"))
      (node (ref "C22") (pin "1") (pinfunction "1_1") (pintype "passive"))
      (node (ref "L4") (pin "1") (pinfunction "1_1") (pintype "passive"))
      (node (ref "U1") (pin "11") (pinfunction "V-_11") (pintype "power_in"))
    )
    (net (code "65") (name "Net-(U2-OFFSET-A)") (class "Default")
      (node (ref "R4") (pin "1") (pinfunction "1_1") (pintype "passive"))
      (node (ref "U2") (pin "12") (pinfunction "OFFSET-A_12") (pintype "output"))
    )
    (net (code "66") (name "Net-(U2-OFFSET-B)") (class "Default")
      (node (ref "R6") (pin "1") (pinfunction "1_1") (pintype "passive"))
      (node (ref "U2") (pin "37") (pinfunction "OFFSET-B_37") (pintype "output"))
    )
    (net (code "67") (name "Net-(U2-VOUT-4)") (class "Default")
      (node (ref "U2") (pin "44") (pinfunction "VOUT-4_44") (pintype "output"))
      (node (ref "U3") (pin "3") (pinfunction "INA+_3") (pintype "input"))
    )
    (net (code "68") (name "Net-(U2-VOUT-5)") (class "Default")
      (node (ref "U2") (pin "42") (pinfunction "VOUT-5_42") (pintype "output"))
      (node (ref "U3") (pin "5") (pinfunction "INB+_5") (pintype "input"))
    )
    (net (code "69") (name "Net-(U2-VOUT-6)") (class "Default")
      (node (ref "U2") (pin "39") (pinfunction "VOUT-6_39") (pintype "output"))
      (node (ref "U3") (pin "10") (pinfunction "INC+_10") (pintype "input"))
    )
    (net (code "70") (name "Net-(U2-VOUT-7)") (class "Default")
      (node (ref "U2") (pin "36") (pinfunction "VOUT-7_36") (pintype "output"))
      (node (ref "U3") (pin "12") (pinfunction "IND+_12") (pintype "input"))
    )
    (net (code "71") (name "Net-(U3-INA-)") (class "Default")
      (node (ref "R13") (pin "1") (pinfunction "1_1") (pintype "passive"))
      (node (ref "U3") (pin "2") (pinfunction "INA-_2") (pintype "input"))
    )
    (net (code "72") (name "Net-(U3-INB-)") (class "Default")
      (node (ref "R15") (pin "1") (pinfunction "1_1") (pintype "passive"))
      (node (ref "U3") (pin "6") (pinfunction "INB-_6") (pintype "input"))
    )
    (net (code "73") (name "Net-(U3-INC-)") (class "Default")
      (node (ref "R16") (pin "1") (pinfunction "1_1") (pintype "passive"))
      (node (ref "U3") (pin "9") (pinfunction "INC-_9") (pintype "input"))
    )
    (net (code "74") (name "Net-(U3-IND-)") (class "Default")
      (node (ref "R17") (pin "1") (pinfunction "1_1") (pintype "passive"))
      (node (ref "U3") (pin "13") (pinfunction "IND-_13") (pintype "input"))
    )
    (net (code "75") (name "Net-(U3-V+)") (class "Default")
      (node (ref "C24") (pin "1") (pinfunction "1_1") (pintype "passive"))
      (node (ref "C26") (pin "1") (pinfunction "1_1") (pintype "passive"))
      (node (ref "C27") (pin "1") (pinfunction "1_1") (pintype "passive"))
      (node (ref "C28") (pin "1") (pinfunction "1_1") (pintype "passive"))
      (node (ref "L5") (pin "2") (pinfunction "2_2") (pintype "passive"))
      (node (ref "U3") (pin "4") (pinfunction "V+_4") (pintype "power_in"))
    )
    (net (code "76") (name "Net-(U3-V-)") (class "Default")
      (node (ref "C35") (pin "1") (pinfunction "1_1") (pintype "passive"))
      (node (ref "C38") (pin "1") (pinfunction "1_1") (pintype "passive"))
      (node (ref "L8") (pin "1") (pinfunction "1_1") (pintype "passive"))
      (node (ref "U3") (pin "11") (pinfunction "V-_11") (pintype "power_in"))
    )
    (net (code "77") (name "REF") (class "Default")
      (node (ref "C15") (pin "2") (pinfunction "2_2") (pintype "passive"))
      (node (ref "C2") (pin "2") (pinfunction "2_2") (pintype "passive"))
      (node (ref "U2") (pin "43") (pinfunction "REF-B_43") (pintype "input"))
      (node (ref "U2") (pin "6") (pinfunction "REF-A_6") (pintype "input"))
    )
    (net (code "78") (name "unconnected-(U2-NC-Pad14)") (class "Default")
      (node (ref "U2") (pin "14") (pinfunction "NC_14") (pintype "passive+no_connect"))
    )
    (net (code "79") (name "unconnected-(U2-NC-Pad22)") (class "Default")
      (node (ref "U2") (pin "22") (pinfunction "NC_22") (pintype "passive+no_connect"))
    )
    (net (code "80") (name "unconnected-(U2-NC-Pad23)") (class "Default")
      (node (ref "U2") (pin "23") (pinfunction "NC_23") (pintype "passive+no_connect"))
    )
    (net (code "81") (name "unconnected-(U2-NC-Pad28)") (class "Default")
      (node (ref "U2") (pin "28") (pinfunction "NC_28") (pintype "passive+no_connect"))
    )
    (net (code "82") (name "unconnected-(U2-NC-Pad31)") (class "Default")
      (node (ref "U2") (pin "31") (pinfunction "NC_31") (pintype "passive+no_connect"))
    )
    (net (code "83") (name "unconnected-(U2-NC-Pad32)") (class "Default")
      (node (ref "U2") (pin "32") (pinfunction "NC_32") (pintype "passive+no_connect"))
    )
    (net (code "84") (name "unconnected-(U2-NC-Pad35)") (class "Default")
      (node (ref "U2") (pin "35") (pinfunction "NC_35") (pintype "passive+no_connect"))
    )
    (net (code "85") (name "unconnected-(U2-NC-Pad45)") (class "Default")
      (node (ref "U2") (pin "45") (pinfunction "NC_45") (pintype "passive+no_connect"))
    )
    (net (code "86") (name "unconnected-(U2-NC-Pad53)") (class "Default")
      (node (ref "U2") (pin "53") (pinfunction "NC_53") (pintype "passive+no_connect"))
    )
  )
)
